# NicoLase_Arduino_Shield.net
KiCad netlist of a schematic drawn in EAGLE
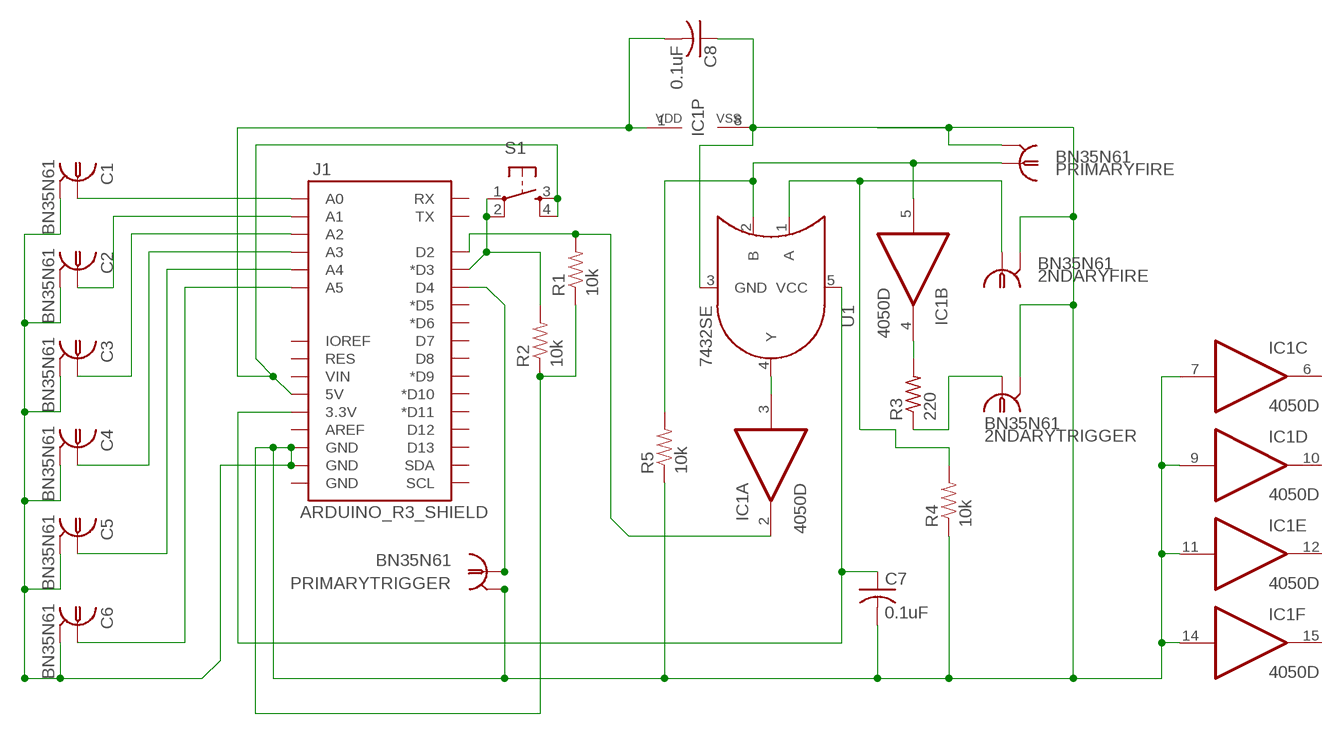
[diagram p0: schematic, sheet 1]

(export (version "E")
  (design (tool "Eeschema 10.0.6"))
  (components
    (comp (ref "2NDARYFIRE")
      (value "BN35N61")
      (footprint "eagle-import:B35N61")
      (libsource (lib "eagle-import") (part "BN35N61"))
    )
    (comp (ref "2NDARYTRIGGER")
      (value "BN35N61")
      (footprint "eagle-import:B35N61")
      (libsource (lib "eagle-import") (part "BN35N61"))
    )
    (comp (ref "C1")
      (value "BN35N61")
      (footprint "eagle-import:B35N61")
      (libsource (lib "eagle-import") (part "BN35N61"))
    )
    (comp (ref "C2")
      (value "BN35N61")
      (footprint "eagle-import:B35N61")
      (libsource (lib "eagle-import") (part "BN35N61"))
    )
    (comp (ref "C3")
      (value "BN35N61")
      (footprint "eagle-import:B35N61")
      (libsource (lib "eagle-import") (part "BN35N61"))
    )
    (comp (ref "C4")
      (value "BN35N61")
      (footprint "eagle-import:B35N61")
      (libsource (lib "eagle-import") (part "BN35N61"))
    )
    (comp (ref "C5")
      (value "BN35N61")
      (footprint "eagle-import:B35N61")
      (libsource (lib "eagle-import") (part "BN35N61"))
    )
    (comp (ref "C6")
      (value "BN35N61")
      (footprint "eagle-import:B35N61")
      (libsource (lib "eagle-import") (part "BN35N61"))
    )
    (comp (ref "C7")
      (value "0.1uF")
      (footprint "eagle-import:C1206")
      (libsource (lib "eagle-import") (part "C-USC1206"))
    )
    (comp (ref "C8")
      (value "0.1uF")
      (footprint "eagle-import:C1206")
      (libsource (lib "eagle-import") (part "C-USC1206"))
    )
    (comp (ref "IC1")
      (value "4050D")
      (footprint "eagle-import:SO16")
      (libsource (lib "eagle-import") (part "4050D"))
    )
    (comp (ref "J1")
      (value "ARDUINO_R3_SHIELD")
      (footprint "eagle-import:UNO_R3_SHIELD")
      (libsource (lib "eagle-import") (part "ARDUINO_R3_SHIELD"))
    )
    (comp (ref "PRIMARYFIRE")
      (value "BN35N61")
      (footprint "eagle-import:B35N61")
      (libsource (lib "eagle-import") (part "BN35N61"))
    )
    (comp (ref "PRIMARYTRIGGER")
      (value "BN35N61")
      (footprint "eagle-import:B35N61")
      (libsource (lib "eagle-import") (part "BN35N61"))
    )
    (comp (ref "R1")
      (value "10k")
      (footprint "eagle-import:1206")
      (libsource (lib "eagle-import") (part "SparkFun-Resistors_RESISTOR1206"))
    )
    (comp (ref "R2")
      (value "10k")
      (footprint "eagle-import:1206")
      (libsource (lib "eagle-import") (part "RESISTOR1206"))
    )
    (comp (ref "R3")
      (value "220")
      (footprint "eagle-import:M1206")
      (libsource (lib "eagle-import") (part "R-US_M1206"))
    )
    (comp (ref "R4")
      (value "10k")
      (footprint "eagle-import:1206")
      (libsource (lib "eagle-import") (part "SparkFun-Resistors_RESISTOR1206"))
    )
    (comp (ref "R5")
      (value "10k")
      (footprint "eagle-import:1206")
      (libsource (lib "eagle-import") (part "SparkFun-Resistors_RESISTOR1206"))
    )
    (comp (ref "S1")
      (value "TAC_SWITCHPTH")
      (footprint "eagle-import:TACTILE-PTH")
      (libsource (lib "eagle-import") (part "TAC_SWITCHPTH"))
    )
    (comp (ref "U1")
      (value "7432SE")
      (footprint "eagle-import:SOT353")
      (libsource (lib "eagle-import") (part "7432SE"))
    )
  )
  (nets
    (net (code "1") (name "Net-(2NDARYTRIGGER-Pad1)") (class "Default")
      (node (ref "2NDARYTRIGGER") (pin "1") (pinfunction "1_1") (pintype "passive"))
      (node (ref "R3") (pin "1") (pinfunction "1_1") (pintype "passive"))
    )
    (net (code "2") (name "Net-(C1-Pad1)") (class "Default")
      (node (ref "C1") (pin "1") (pinfunction "1_1") (pintype "passive"))
      (node (ref "J1") (pin "A0") (pinfunction "A0_A0") (pintype "bidirectional"))
    )
    (net (code "3") (name "Net-(C2-Pad1)") (class "Default")
      (node (ref "C2") (pin "1") (pinfunction "1_1") (pintype "passive"))
      (node (ref "J1") (pin "A1") (pinfunction "A1_A1") (pintype "bidirectional"))
    )
    (net (code "4") (name "Net-(C3-Pad1)") (class "Default")
      (node (ref "C3") (pin "1") (pinfunction "1_1") (pintype "passive"))
      (node (ref "J1") (pin "A2") (pinfunction "A2_A2") (pintype "bidirectional"))
    )
    (net (code "5") (name "Net-(C4-Pad1)") (class "Default")
      (node (ref "C4") (pin "1") (pinfunction "1_1") (pintype "passive"))
      (node (ref "J1") (pin "A3") (pinfunction "A3_A3") (pintype "bidirectional"))
    )
    (net (code "6") (name "Net-(C5-Pad1)") (class "Default")
      (node (ref "C5") (pin "1") (pinfunction "1_1") (pintype "passive"))
      (node (ref "J1") (pin "A4") (pinfunction "A4_A4") (pintype "bidirectional"))
    )
    (net (code "7") (name "Net-(C6-Pad1)") (class "Default")
      (node (ref "C6") (pin "1") (pinfunction "1_1") (pintype "passive"))
      (node (ref "J1") (pin "A5") (pinfunction "A5_A5") (pintype "bidirectional"))
    )
    (net (code "8") (name "Net-(IC1A-I)") (class "Default")
      (node (ref "IC1") (pin "3") (pinfunction "I_3") (pintype "input"))
      (node (ref "U1") (pin "4") (pinfunction "Y_4") (pintype "bidirectional"))
    )
    (net (code "9") (name "Net-(IC1A-O)") (class "Default")
      (node (ref "IC1") (pin "2") (pinfunction "O_2") (pintype "output"))
      (node (ref "J1") (pin "D2") (pinfunction "D2_D2") (pintype "bidirectional"))
      (node (ref "R1") (pin "2") (pinfunction "2_2") (pintype "passive"))
    )
    (net (code "10") (name "Net-(IC1B-I)") (class "Default")
      (node (ref "IC1") (pin "5") (pinfunction "I_5") (pintype "input"))
      (node (ref "PRIMARYFIRE") (pin "1") (pinfunction "1_1") (pintype "passive"))
      (node (ref "R5") (pin "2") (pinfunction "2_2") (pintype "passive"))
      (node (ref "U1") (pin "2") (pinfunction "B_2") (pintype "bidirectional"))
    )
    (net (code "11") (name "Net-(IC1B-O)") (class "Default")
      (node (ref "IC1") (pin "4") (pinfunction "O_4") (pintype "output"))
      (node (ref "R3") (pin "2") (pinfunction "2_2") (pintype "passive"))
    )
    (net (code "12") (name "Net-(IC1C-I)") (class "Default")
      (node (ref "2NDARYFIRE") (pin "2") (pinfunction "2_2") (pintype "passive"))
      (node (ref "2NDARYFIRE") (pin "3") (pinfunction "2_3") (pintype "passive"))
      (node (ref "2NDARYFIRE") (pin "4") (pinfunction "2_4") (pintype "passive"))
      (node (ref "2NDARYFIRE") (pin "5") (pinfunction "2_5") (pintype "passive"))
      (node (ref "2NDARYTRIGGER") (pin "2") (pinfunction "2_2") (pintype "passive"))
      (node (ref "2NDARYTRIGGER") (pin "3") (pinfunction "2_3") (pintype "passive"))
      (node (ref "2NDARYTRIGGER") (pin "4") (pinfunction "2_4") (pintype "passive"))
      (node (ref "2NDARYTRIGGER") (pin "5") (pinfunction "2_5") (pintype "passive"))
      (node (ref "C1") (pin "2") (pinfunction "2_2") (pintype "passive"))
      (node (ref "C1") (pin "3") (pinfunction "2_3") (pintype "passive"))
      (node (ref "C1") (pin "4") (pinfunction "2_4") (pintype "passive"))
      (node (ref "C1") (pin "5") (pinfunction "2_5") (pintype "passive"))
      (node (ref "C2") (pin "2") (pinfunction "2_2") (pintype "passive"))
      (node (ref "C2") (pin "3") (pinfunction "2_3") (pintype "passive"))
      (node (ref "C2") (pin "4") (pinfunction "2_4") (pintype "passive"))
      (node (ref "C2") (pin "5") (pinfunction "2_5") (pintype "passive"))
      (node (ref "C3") (pin "2") (pinfunction "2_2") (pintype "passive"))
      (node (ref "C3") (pin "3") (pinfunction "2_3") (pintype "passive"))
      (node (ref "C3") (pin "4") (pinfunction "2_4") (pintype "passive"))
      (node (ref "C3") (pin "5") (pinfunction "2_5") (pintype "passive"))
      (node (ref "C4") (pin "2") (pinfunction "2_2") (pintype "passive"))
      (node (ref "C4") (pin "3") (pinfunction "2_3") (pintype "passive"))
      (node (ref "C4") (pin "4") (pinfunction "2_4") (pintype "passive"))
      (node (ref "C4") (pin "5") (pinfunction "2_5") (pintype "passive"))
      (node (ref "C5") (pin "2") (pinfunction "2_2") (pintype "passive"))
      (node (ref "C5") (pin "3") (pinfunction "2_3") (pintype "passive"))
      (node (ref "C5") (pin "4") (pinfunction "2_4") (pintype "passive"))
      (node (ref "C5") (pin "5") (pinfunction "2_5") (pintype "passive"))
      (node (ref "C6") (pin "2") (pinfunction "2_2") (pintype "passive"))
      (node (ref "C6") (pin "3") (pinfunction "2_3") (pintype "passive"))
      (node (ref "C6") (pin "4") (pinfunction "2_4") (pintype "passive"))
      (node (ref "C6") (pin "5") (pinfunction "2_5") (pintype "passive"))
      (node (ref "C7") (pin "2") (pinfunction "2_2") (pintype "passive"))
      (node (ref "C8") (pin "1") (pinfunction "1_1") (pintype "passive"))
      (node (ref "IC1") (pin "11") (pinfunction "I_11") (pintype "input"))
      (node (ref "IC1") (pin "14") (pinfunction "I_14") (pintype "input"))
      (node (ref "IC1") (pin "7") (pinfunction "I_7") (pintype "input"))
      (node (ref "IC1") (pin "8") (pinfunction "VSS_8") (pintype "power_in"))
      (node (ref "IC1") (pin "9") (pinfunction "I_9") (pintype "input"))
      (node (ref "J1") (pin "GND@1") (pinfunction "GND_GND@1") (pintype "bidirectional"))
      (node (ref "J1") (pin "GND@2") (pinfunction "GND_GND@2") (pintype "bidirectional"))
      (node (ref "PRIMARYFIRE") (pin "2") (pinfunction "2_2") (pintype "passive"))
      (node (ref "PRIMARYFIRE") (pin "3") (pinfunction "2_3") (pintype "passive"))
      (node (ref "PRIMARYFIRE") (pin "4") (pinfunction "2_4") (pintype "passive"))
      (node (ref "PRIMARYFIRE") (pin "5") (pinfunction "2_5") (pintype "passive"))
      (node (ref "PRIMARYTRIGGER") (pin "2") (pinfunction "2_2") (pintype "passive"))
      (node (ref "PRIMARYTRIGGER") (pin "3") (pinfunction "2_3") (pintype "passive"))
      (node (ref "PRIMARYTRIGGER") (pin "4") (pinfunction "2_4") (pintype "passive"))
      (node (ref "PRIMARYTRIGGER") (pin "5") (pinfunction "2_5") (pintype "passive"))
      (node (ref "R1") (pin "1") (pinfunction "1_1") (pintype "passive"))
      (node (ref "R2") (pin "1") (pinfunction "1_1") (pintype "passive"))
      (node (ref "R4") (pin "1") (pinfunction "1_1") (pintype "passive"))
      (node (ref "R5") (pin "1") (pinfunction "1_1") (pintype "passive"))
      (node (ref "U1") (pin "3") (pinfunction "GND_3") (pintype "bidirectional"))
    )
    (net (code "13") (name "Net-(IC1G-VDD)") (class "Default")
      (node (ref "C8") (pin "2") (pinfunction "2_2") (pintype "passive"))
      (node (ref "IC1") (pin "1") (pinfunction "VDD_1") (pintype "power_in"))
      (node (ref "J1") (pin "5V") (pinfunction "5V_5V") (pintype "bidirectional"))
      (node (ref "S1") (pin "3") (pinfunction "3_3") (pintype "passive"))
      (node (ref "S1") (pin "4") (pinfunction "4_4") (pintype "passive"))
    )
    (net (code "14") (name "Net-(J1-*D3)") (class "Default")
      (node (ref "J1") (pin "D3") (pinfunction "*D3_D3") (pintype "bidirectional"))
      (node (ref "R2") (pin "2") (pinfunction "2_2") (pintype "passive"))
      (node (ref "S1") (pin "1") (pinfunction "1_1") (pintype "passive"))
      (node (ref "S1") (pin "2") (pinfunction "2_2") (pintype "passive"))
    )
    (net (code "15") (name "Net-(J1-PadD4)") (class "Default")
      (node (ref "J1") (pin "D4") (pinfunction "D4_D4") (pintype "bidirectional"))
      (node (ref "PRIMARYTRIGGER") (pin "1") (pinfunction "1_1") (pintype "passive"))
    )
    (net (code "16") (name "Net-(U1-A)") (class "Default")
      (node (ref "2NDARYFIRE") (pin "1") (pinfunction "1_1") (pintype "passive"))
      (node (ref "R4") (pin "2") (pinfunction "2_2") (pintype "passive"))
      (node (ref "U1") (pin "1") (pinfunction "A_1") (pintype "bidirectional"))
    )
    (net (code "17") (name "Net-(U1-VCC)") (class "Default")
      (node (ref "C7") (pin "1") (pinfunction "1_1") (pintype "passive"))
      (node (ref "J1") (pin "3.3V") (pinfunction "3.3V_3.3V") (pintype "bidirectional"))
      (node (ref "U1") (pin "5") (pinfunction "VCC_5") (pintype "bidirectional"))
    )
    (net (code "18") (name "unconnected-(IC1C-O-Pad6)") (class "Default")
      (node (ref "IC1") (pin "6") (pinfunction "O_6") (pintype "output"))
    )
    (net (code "19") (name "unconnected-(IC1D-O-Pad10)") (class "Default")
      (node (ref "IC1") (pin "10") (pinfunction "O_10") (pintype "output"))
    )
    (net (code "20") (name "unconnected-(IC1E-O-Pad12)") (class "Default")
      (node (ref "IC1") (pin "12") (pinfunction "O_12") (pintype "output"))
    )
    (net (code "21") (name "unconnected-(IC1F-O-Pad15)") (class "Default")
      (node (ref "IC1") (pin "15") (pinfunction "O_15") (pintype "output"))
    )
    (net (code "22") (name "unconnected-(J1-*D5-PadD5)") (class "Default")
      (node (ref "J1") (pin "D5") (pinfunction "*D5_D5") (pintype "bidirectional"))
    )
    (net (code "23") (name "unconnected-(J1-*D6-PadD6)") (class "Default")
      (node (ref "J1") (pin "D6") (pinfunction "*D6_D6") (pintype "bidirectional"))
    )
    (net (code "24") (name "unconnected-(J1-*D9-PadD9)") (class "Default")
      (node (ref "J1") (pin "D9") (pinfunction "*D9_D9") (pintype "bidirectional"))
    )
    (net (code "25") (name "unconnected-(J1-*D10-PadD10)") (class "Default")
      (node (ref "J1") (pin "D10") (pinfunction "*D10_D10") (pintype "bidirectional"))
    )
    (net (code "26") (name "unconnected-(J1-*D11-PadD11)") (class "Default")
      (node (ref "J1") (pin "D11") (pinfunction "*D11_D11") (pintype "bidirectional"))
    )
    (net (code "27") (name "unconnected-(J1-GND-PadGND@0)") (class "Default")
      (node (ref "J1") (pin "GND@0") (pinfunction "GND_GND@0") (pintype "bidirectional"))
    )
    (net (code "28") (name "unconnected-(J1-PadAREF)") (class "Default")
      (node (ref "J1") (pin "AREF") (pinfunction "AREF_AREF") (pintype "bidirectional"))
    )
    (net (code "29") (name "unconnected-(J1-PadD7)") (class "Default")
      (node (ref "J1") (pin "D7") (pinfunction "D7_D7") (pintype "bidirectional"))
    )
    (net (code "30") (name "unconnected-(J1-PadD8)") (class "Default")
      (node (ref "J1") (pin "D8") (pinfunction "D8_D8") (pintype "bidirectional"))
    )
    (net (code "31") (name "unconnected-(J1-PadD12)") (class "Default")
      (node (ref "J1") (pin "D12") (pinfunction "D12_D12") (pintype "bidirectional"))
    )
    (net (code "32") (name "unconnected-(J1-PadD13)") (class "Default")
      (node (ref "J1") (pin "D13") (pinfunction "D13_D13") (pintype "bidirectional"))
    )
    (net (code "33") (name "unconnected-(J1-PadIOREF)") (class "Default")
      (node (ref "J1") (pin "IOREF") (pinfunction "IOREF_IOREF") (pintype "bidirectional"))
    )
    (net (code "34") (name "unconnected-(J1-PadRES)") (class "Default")
      (node (ref "J1") (pin "RES") (pinfunction "RES_RES") (pintype "bidirectional"))
    )
    (net (code "35") (name "unconnected-(J1-PadRX)") (class "Default")
      (node (ref "J1") (pin "RX") (pinfunction "RX_RX") (pintype "bidirectional"))
    )
    (net (code "36") (name "unconnected-(J1-PadSCL)") (class "Default")
      (node (ref "J1") (pin "SCL") (pinfunction "SCL_SCL") (pintype "bidirectional"))
    )
    (net (code "37") (name "unconnected-(J1-PadSDA)") (class "Default")
      (node (ref "J1") (pin "SDA") (pinfunction "SDA_SDA") (pintype "bidirectional"))
    )
    (net (code "38") (name "unconnected-(J1-PadTX)") (class "Default")
      (node (ref "J1") (pin "TX") (pinfunction "TX_TX") (pintype "bidirectional"))
    )
    (net (code "39") (name "unconnected-(J1-PadVIN)") (class "Default")
      (node (ref "J1") (pin "VIN") (pinfunction "VIN_VIN") (pintype "bidirectional"))
    )
  )
)
